# MM_Motor_Driver.net
KiCad netlist of a schematic drawn in Altium Designer
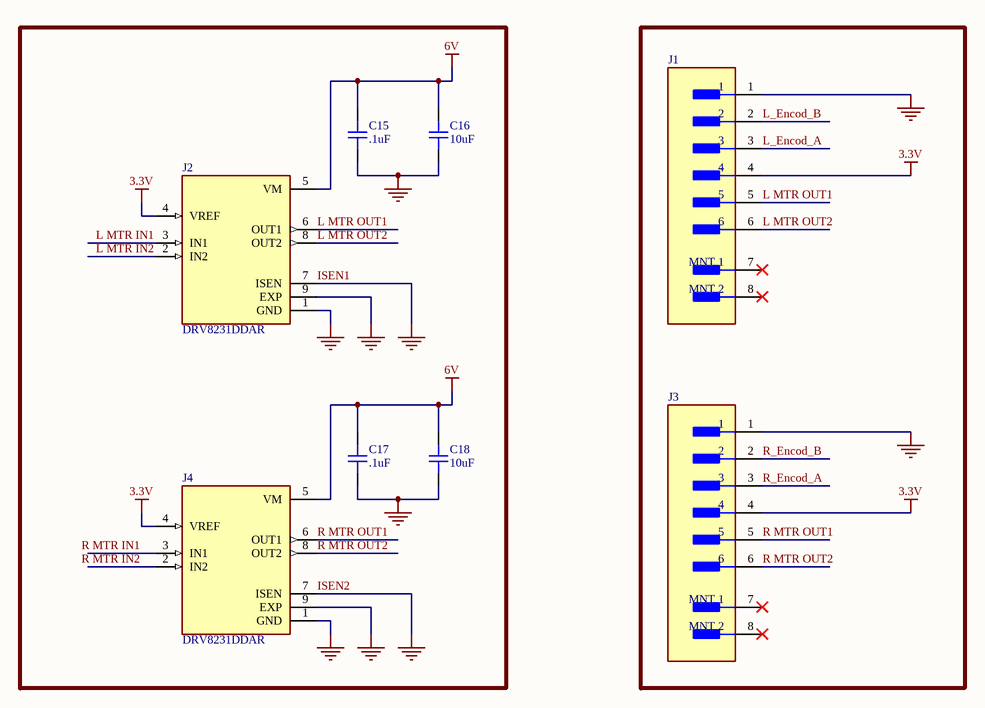
[diagram p0: MM_Motor_Driver.SchDoc]

(export (version "E")
  (design (tool "Eeschema 10.0.6"))
  (components
    (comp (ref "C15")
      (value ".1uF")
      (footprint "CAP_0603")
      (description "Capacitor SMD 0603")
      (libsource (lib "Schematic-Lib-PhilsLab") (part "CAP_0603"))
    )
    (comp (ref "C16")
      (value "10uF")
      (footprint "CAP_0603")
      (description "Capacitor SMD 0603")
      (libsource (lib "Schematic-Lib-PhilsLab") (part "CAP_0603"))
    )
    (comp (ref "C17")
      (value ".1uF")
      (footprint "CAP_0603")
      (description "Capacitor SMD 0603")
      (libsource (lib "Schematic-Lib-PhilsLab") (part "CAP_0603"))
    )
    (comp (ref "C18")
      (value "10uF")
      (footprint "CAP_0603")
      (description "Capacitor SMD 0603")
      (libsource (lib "Schematic-Lib-PhilsLab") (part "CAP_0603"))
    )
    (comp (ref "J1")
      (value "BM06B-SRSS-TBT(LF)(SN)")
      (footprint "FP-BM06B-SRSS-TBT_LF_SN-MFG")
      (description "CONN HEADER SMD 6POS 1MM")
      (libsource (lib "Altium Content Vault") (part "ed24c53d9ba001d1a2a686240a95171"))
    )
    (comp (ref "J2")
      (value "DRV8231DDAR")
      (footprint "IC_DRV8231DDAR")
      (description "35-V, 3.7-A H-bridge motor driver with integrated current regulation")
      (libsource (lib "Schematic-Lib-PhilsLab") (part "DRV8231DDAR"))
    )
    (comp (ref "J3")
      (value "BM06B-SRSS-TBT(LF)(SN)")
      (footprint "FP-BM06B-SRSS-TBT_LF_SN-MFG")
      (description "CONN HEADER SMD 6POS 1MM")
      (libsource (lib "Altium Content Vault") (part "ed24c53d9ba001d1a2a686240a95171"))
    )
    (comp (ref "J4")
      (value "DRV8231DDAR")
      (footprint "IC_DRV8231DDAR")
      (description "35-V, 3.7-A H-bridge motor driver with integrated current regulation")
      (libsource (lib "Schematic-Lib-PhilsLab") (part "DRV8231DDAR"))
    )
  )
  (nets
    (net (code "1") (name "/L MTR IN1") (class "Default")
      (node (ref "J2") (pin "3") (pinfunction "IN1_3") (pintype "input"))
    )
    (net (code "2") (name "/L MTR IN2") (class "Default")
      (node (ref "J2") (pin "2") (pinfunction "IN2_2") (pintype "input"))
    )
    (net (code "3") (name "/L MTR OUT1") (class "Default")
      (node (ref "J1") (pin "5") (pinfunction "5_5") (pintype "passive"))
      (node (ref "J2") (pin "6") (pinfunction "OUT1_6") (pintype "output"))
    )
    (net (code "4") (name "/L MTR OUT2") (class "Default")
      (node (ref "J1") (pin "6") (pinfunction "6_6") (pintype "passive"))
      (node (ref "J2") (pin "8") (pinfunction "OUT2_8") (pintype "output"))
    )
    (net (code "5") (name "/L_Encod_A") (class "Default")
      (node (ref "J1") (pin "3") (pinfunction "3_3") (pintype "passive"))
    )
    (net (code "6") (name "/L_Encod_B") (class "Default")
      (node (ref "J1") (pin "2") (pinfunction "2_2") (pintype "passive"))
    )
    (net (code "7") (name "/R MTR IN1") (class "Default")
      (node (ref "J4") (pin "3") (pinfunction "IN1_3") (pintype "input"))
    )
    (net (code "8") (name "/R MTR IN2") (class "Default")
      (node (ref "J4") (pin "2") (pinfunction "IN2_2") (pintype "input"))
    )
    (net (code "9") (name "/R MTR OUT1") (class "Default")
      (node (ref "J3") (pin "5") (pinfunction "5_5") (pintype "passive"))
      (node (ref "J4") (pin "6") (pinfunction "OUT1_6") (pintype "output"))
    )
    (net (code "10") (name "/R MTR OUT2") (class "Default")
      (node (ref "J3") (pin "6") (pinfunction "6_6") (pintype "passive"))
      (node (ref "J4") (pin "8") (pinfunction "OUT2_8") (pintype "output"))
    )
    (net (code "11") (name "/R_Encod_A") (class "Default")
      (node (ref "J3") (pin "3") (pinfunction "3_3") (pintype "passive"))
    )
    (net (code "12") (name "/R_Encod_B") (class "Default")
      (node (ref "J3") (pin "2") (pinfunction "2_2") (pintype "passive"))
    )
    (net (code "13") (name "3.3V") (class "Default")
      (node (ref "J1") (pin "4") (pinfunction "4_4") (pintype "passive"))
      (node (ref "J2") (pin "4") (pinfunction "VREF_4") (pintype "input"))
      (node (ref "J3") (pin "4") (pinfunction "4_4") (pintype "passive"))
      (node (ref "J4") (pin "4") (pinfunction "VREF_4") (pintype "input"))
    )
    (net (code "14") (name "6V") (class "Default")
      (node (ref "C15") (pin "2") (pinfunction "2_2") (pintype "passive"))
      (node (ref "C16") (pin "2") (pinfunction "2_2") (pintype "passive"))
      (node (ref "C17") (pin "2") (pinfunction "2_2") (pintype "passive"))
      (node (ref "C18") (pin "2") (pinfunction "2_2") (pintype "passive"))
      (node (ref "J2") (pin "5") (pinfunction "VM_5") (pintype "power_in"))
      (node (ref "J4") (pin "5") (pinfunction "VM_5") (pintype "power_in"))
    )
    (net (code "15") (name "GND") (class "Default")
      (node (ref "C15") (pin "1") (pinfunction "1_1") (pintype "passive"))
      (node (ref "C16") (pin "1") (pinfunction "1_1") (pintype "passive"))
      (node (ref "C17") (pin "1") (pinfunction "1_1") (pintype "passive"))
      (node (ref "C18") (pin "1") (pinfunction "1_1") (pintype "passive"))
      (node (ref "J1") (pin "1") (pinfunction "1_1") (pintype "passive"))
      (node (ref "J2") (pin "1") (pinfunction "GND_1") (pintype "power_in"))
      (node (ref "J2") (pin "7") (pinfunction "ISEN_7") (pintype "power_in"))
      (node (ref "J2") (pin "9") (pinfunction "EXP_9") (pintype "power_in"))
      (node (ref "J3") (pin "1") (pinfunction "1_1") (pintype "passive"))
      (node (ref "J4") (pin "1") (pinfunction "GND_1") (pintype "power_in"))
      (node (ref "J4") (pin "7") (pinfunction "ISEN_7") (pintype "power_in"))
      (node (ref "J4") (pin "9") (pinfunction "EXP_9") (pintype "power_in"))
    )
    (net (code "16") (name "unconnected-(J1-MNT_1-Pad7)") (class "Default")
      (node (ref "J1") (pin "7") (pinfunction "MNT_1_7") (pintype "passive+no_connect"))
    )
    (net (code "17") (name "unconnected-(J1-MNT_2-Pad8)") (class "Default")
      (node (ref "J1") (pin "8") (pinfunction "MNT_2_8") (pintype "passive+no_connect"))
    )
    (net (code "18") (name "unconnected-(J3-MNT_1-Pad7)") (class "Default")
      (node (ref "J3") (pin "7") (pinfunction "MNT_1_7") (pintype "passive+no_connect"))
    )
    (net (code "19") (name "unconnected-(J3-MNT_2-Pad8)") (class "Default")
      (node (ref "J3") (pin "8") (pinfunction "MNT_2_8") (pintype "passive+no_connect"))
    )
  )
)
